# board.net
KiCad netlist of a schematic drawn in EAGLE
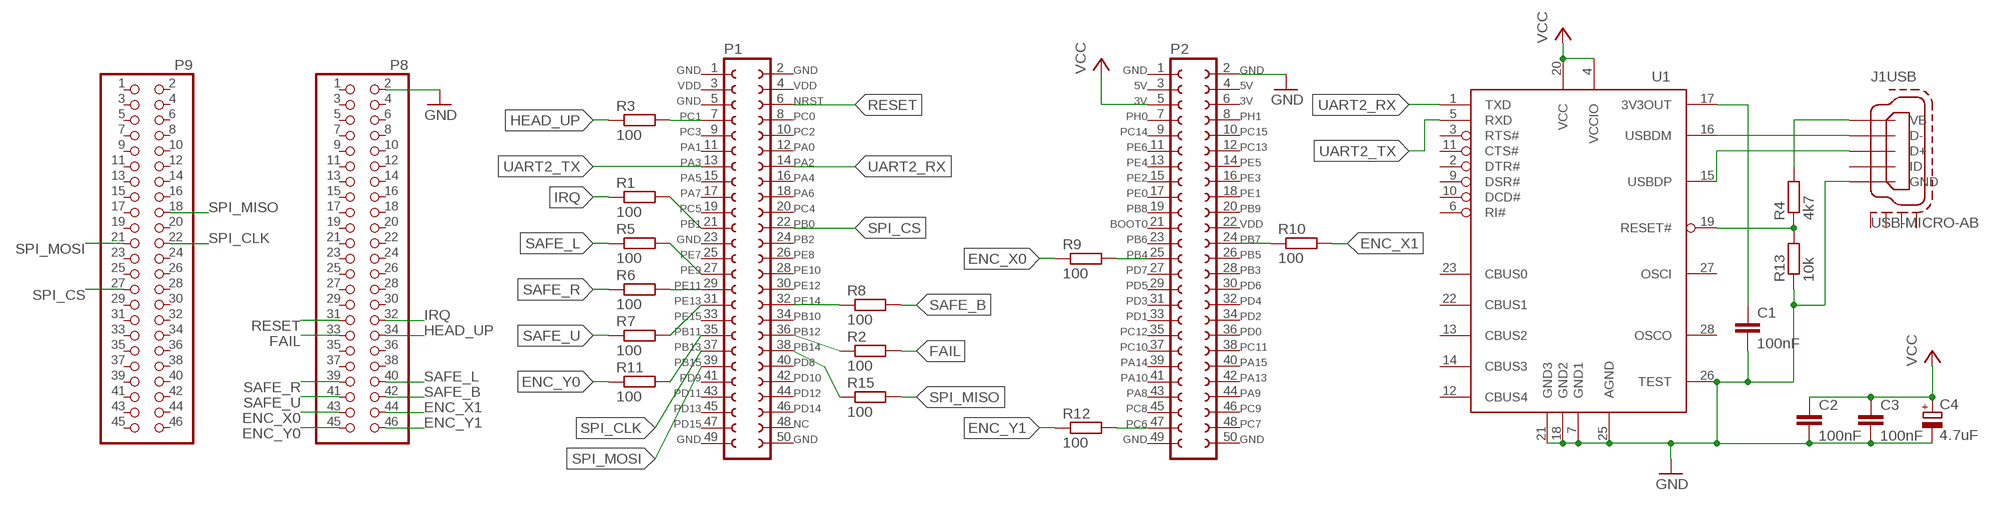
[diagram p0: schematic, sheet 1]

(export (version "E")
  (design (tool "Eeschema 10.0.6"))
  (components
    (comp (ref "C1")
      (value "100nF")
      (footprint "eagle-import:C025-024X044")
      (libsource (lib "eagle-import") (part "C-EU025-024X044"))
    )
    (comp (ref "C2")
      (value "100nF")
      (footprint "eagle-import:C025-024X044")
      (libsource (lib "eagle-import") (part "C-EU025-024X044"))
    )
    (comp (ref "C3")
      (value "100nF")
      (footprint "eagle-import:C025-024X044")
      (libsource (lib "eagle-import") (part "C-EU025-024X044"))
    )
    (comp (ref "C4")
      (value "4.7uF")
      (footprint "eagle-import:E15-5")
      (libsource (lib "eagle-import") (part "CPOL-EUE15-5AXIAL"))
    )
    (comp (ref "J1")
      (value "USB-MICRO-AB")
      (footprint "eagle-import:USB-MICRO-AB")
      (libsource (lib "eagle-import") (part "USB-MICRO-AB"))
    )
    (comp (ref "P1")
      (value "PIN-F-2X25-DISC-P1")
      (footprint "eagle-import:PIN-F-2X25")
      (libsource (lib "eagle-import") (part "PIN-F-2X25-DISC-P1"))
    )
    (comp (ref "P2")
      (value "PIN-F-2X25-DISC-P2")
      (footprint "eagle-import:PIN-F-2X25")
      (libsource (lib "eagle-import") (part "PIN-F-2X25-DISC-P2"))
    )
    (comp (ref "P8")
      (value "PIN-M-2X23")
      (footprint "eagle-import:PIN-M-2X23")
      (libsource (lib "eagle-import") (part "PIN-M-2X23"))
    )
    (comp (ref "P9")
      (value "PIN-M-2X23")
      (footprint "eagle-import:PIN-M-2X23")
      (libsource (lib "eagle-import") (part "PIN-M-2X23"))
    )
    (comp (ref "R1")
      (value "100")
      (footprint "eagle-import:0204_5")
      (libsource (lib "eagle-import") (part "R_EU"))
    )
    (comp (ref "R2")
      (value "100")
      (footprint "eagle-import:0204_5")
      (libsource (lib "eagle-import") (part "R_EU"))
    )
    (comp (ref "R3")
      (value "100")
      (footprint "eagle-import:0204_5")
      (libsource (lib "eagle-import") (part "R_EU"))
    )
    (comp (ref "R4")
      (value "4k7")
      (footprint "eagle-import:0204_5")
      (libsource (lib "eagle-import") (part "R_EU"))
    )
    (comp (ref "R5")
      (value "100")
      (footprint "eagle-import:0204_5")
      (libsource (lib "eagle-import") (part "R_EU"))
    )
    (comp (ref "R6")
      (value "100")
      (footprint "eagle-import:0204_5")
      (libsource (lib "eagle-import") (part "R_EU"))
    )
    (comp (ref "R7")
      (value "100")
      (footprint "eagle-import:0204_5")
      (libsource (lib "eagle-import") (part "R_EU"))
    )
    (comp (ref "R8")
      (value "100")
      (footprint "eagle-import:0204_5")
      (libsource (lib "eagle-import") (part "R_EU"))
    )
    (comp (ref "R9")
      (value "100")
      (footprint "eagle-import:0204_5")
      (libsource (lib "eagle-import") (part "R_EU"))
    )
    (comp (ref "R10")
      (value "100")
      (footprint "eagle-import:0204_5")
      (libsource (lib "eagle-import") (part "R_EU"))
    )
    (comp (ref "R11")
      (value "100")
      (footprint "eagle-import:0204_5")
      (libsource (lib "eagle-import") (part "R_EU"))
    )
    (comp (ref "R12")
      (value "100")
      (footprint "eagle-import:0204_5")
      (libsource (lib "eagle-import") (part "R_EU"))
    )
    (comp (ref "R13")
      (value "10k")
      (footprint "eagle-import:0204_5")
      (libsource (lib "eagle-import") (part "R_EU"))
    )
    (comp (ref "R15")
      (value "100")
      (footprint "eagle-import:0204_5")
      (libsource (lib "eagle-import") (part "R_EU"))
    )
    (comp (ref "U1")
      (value "FT232RL")
      (footprint "eagle-import:SSOP28DB")
      (libsource (lib "eagle-import") (part "FT232RL"))
    )
  )
  (nets
    (net (code "1") (name "ENC_X0") (class "Default")
      (node (ref "P8") (pin "43") (pinfunction "43_43") (pintype "passive"))
      (node (ref "R9") (pin "1") (pinfunction "1_1") (pintype "passive"))
    )
    (net (code "2") (name "ENC_X1") (class "Default")
      (node (ref "P8") (pin "44") (pinfunction "44_44") (pintype "passive"))
      (node (ref "R10") (pin "2") (pinfunction "2_2") (pintype "passive"))
    )
    (net (code "3") (name "ENC_Y0") (class "Default")
      (node (ref "P8") (pin "45") (pinfunction "45_45") (pintype "passive"))
      (node (ref "R11") (pin "1") (pinfunction "1_1") (pintype "passive"))
    )
    (net (code "4") (name "ENC_Y1") (class "Default")
      (node (ref "P8") (pin "46") (pinfunction "46_46") (pintype "passive"))
      (node (ref "R12") (pin "1") (pinfunction "1_1") (pintype "passive"))
    )
    (net (code "5") (name "FAIL") (class "Default")
      (node (ref "P8") (pin "33") (pinfunction "33_33") (pintype "passive"))
      (node (ref "R2") (pin "2") (pinfunction "2_2") (pintype "passive"))
    )
    (net (code "6") (name "GND") (class "Default")
      (node (ref "C1") (pin "2") (pinfunction "2_2") (pintype "passive"))
      (node (ref "C2") (pin "2") (pinfunction "2_2") (pintype "passive"))
      (node (ref "C3") (pin "2") (pinfunction "2_2") (pintype "passive"))
      (node (ref "C4") (pin "-") (pinfunction "-_-") (pintype "passive"))
      (node (ref "J1") (pin "P$5") (pinfunction "GND_P$5") (pintype "passive"))
      (node (ref "P2") (pin "2") (pinfunction "2_2") (pintype "passive"))
      (node (ref "P8") (pin "2") (pinfunction "2_2") (pintype "passive"))
      (node (ref "R13") (pin "1") (pinfunction "1_1") (pintype "passive"))
      (node (ref "U1") (pin "18") (pinfunction "GND2_18") (pintype "power_in"))
      (node (ref "U1") (pin "21") (pinfunction "GND3_21") (pintype "power_in"))
      (node (ref "U1") (pin "25") (pinfunction "AGND_25") (pintype "power_in"))
      (node (ref "U1") (pin "26") (pinfunction "TEST_26") (pintype "input"))
      (node (ref "U1") (pin "7") (pinfunction "GND1_7") (pintype "power_in"))
    )
    (net (code "7") (name "HEAD_UP") (class "Default")
      (node (ref "P8") (pin "34") (pinfunction "34_34") (pintype "passive"))
      (node (ref "R3") (pin "1") (pinfunction "1_1") (pintype "passive"))
    )
    (net (code "8") (name "IRQ") (class "Default")
      (node (ref "P8") (pin "32") (pinfunction "32_32") (pintype "passive"))
      (node (ref "R1") (pin "1") (pinfunction "1_1") (pintype "passive"))
    )
    (net (code "9") (name "Net-(J1B-D+)") (class "Default")
      (node (ref "J1") (pin "P$3") (pinfunction "D+_P$3") (pintype "passive"))
      (node (ref "U1") (pin "15") (pinfunction "USBDP_15") (pintype "bidirectional"))
    )
    (net (code "10") (name "Net-(J1B-D-)") (class "Default")
      (node (ref "J1") (pin "P$2") (pinfunction "D-_P$2") (pintype "passive"))
      (node (ref "U1") (pin "16") (pinfunction "USBDM_16") (pintype "bidirectional"))
    )
    (net (code "11") (name "Net-(J1B-VB)") (class "Default")
      (node (ref "J1") (pin "P$1") (pinfunction "VB_P$1") (pintype "passive"))
      (node (ref "R4") (pin "2") (pinfunction "2_2") (pintype "passive"))
    )
    (net (code "12") (name "Net-(P1-Pad7)") (class "Default")
      (node (ref "P1") (pin "7") (pinfunction "7_7") (pintype "passive"))
      (node (ref "R3") (pin "2") (pinfunction "2_2") (pintype "passive"))
    )
    (net (code "13") (name "Net-(P1-Pad21)") (class "Default")
      (node (ref "P1") (pin "21") (pinfunction "21_21") (pintype "passive"))
      (node (ref "R1") (pin "2") (pinfunction "2_2") (pintype "passive"))
    )
    (net (code "14") (name "Net-(P1-Pad27)") (class "Default")
      (node (ref "P1") (pin "27") (pinfunction "27_27") (pintype "passive"))
      (node (ref "R5") (pin "2") (pinfunction "2_2") (pintype "passive"))
    )
    (net (code "15") (name "Net-(P1-Pad29)") (class "Default")
      (node (ref "P1") (pin "29") (pinfunction "29_29") (pintype "passive"))
      (node (ref "R6") (pin "2") (pinfunction "2_2") (pintype "passive"))
    )
    (net (code "16") (name "Net-(P1-Pad31)") (class "Default")
      (node (ref "P1") (pin "31") (pinfunction "31_31") (pintype "passive"))
      (node (ref "R7") (pin "2") (pinfunction "2_2") (pintype "passive"))
    )
    (net (code "17") (name "Net-(P1-Pad32)") (class "Default")
      (node (ref "P1") (pin "32") (pinfunction "32_32") (pintype "passive"))
      (node (ref "R8") (pin "1") (pinfunction "1_1") (pintype "passive"))
    )
    (net (code "18") (name "Net-(P1-Pad35)") (class "Default")
      (node (ref "P1") (pin "35") (pinfunction "35_35") (pintype "passive"))
      (node (ref "R11") (pin "2") (pinfunction "2_2") (pintype "passive"))
    )
    (net (code "19") (name "Net-(P1-Pad36)") (class "Default")
      (node (ref "P1") (pin "36") (pinfunction "36_36") (pintype "passive"))
      (node (ref "R2") (pin "1") (pinfunction "1_1") (pintype "passive"))
    )
    (net (code "20") (name "Net-(P1-Pad38)") (class "Default")
      (node (ref "P1") (pin "38") (pinfunction "38_38") (pintype "passive"))
      (node (ref "R15") (pin "1") (pinfunction "1_1") (pintype "passive"))
    )
    (net (code "21") (name "Net-(P2-Pad24)") (class "Default")
      (node (ref "P2") (pin "24") (pinfunction "24_24") (pintype "passive"))
      (node (ref "R10") (pin "1") (pinfunction "1_1") (pintype "passive"))
    )
    (net (code "22") (name "Net-(P2-Pad25)") (class "Default")
      (node (ref "P2") (pin "25") (pinfunction "25_25") (pintype "passive"))
      (node (ref "R9") (pin "2") (pinfunction "2_2") (pintype "passive"))
    )
    (net (code "23") (name "Net-(P2-Pad47)") (class "Default")
      (node (ref "P2") (pin "47") (pinfunction "47_47") (pintype "passive"))
      (node (ref "R12") (pin "2") (pinfunction "2_2") (pintype "passive"))
    )
    (net (code "24") (name "Net-(U1-3V3OUT)") (class "Default")
      (node (ref "C1") (pin "1") (pinfunction "1_1") (pintype "passive"))
      (node (ref "U1") (pin "17") (pinfunction "3V3OUT_17") (pintype "output"))
    )
    (net (code "25") (name "Net-(U1-RESET#)") (class "Default")
      (node (ref "R13") (pin "2") (pinfunction "2_2") (pintype "passive"))
      (node (ref "R4") (pin "1") (pinfunction "1_1") (pintype "passive"))
      (node (ref "U1") (pin "19") (pinfunction "RESET#_19") (pintype "input"))
    )
    (net (code "26") (name "RESET") (class "Default")
      (node (ref "P1") (pin "6") (pinfunction "6_6") (pintype "passive"))
      (node (ref "P8") (pin "31") (pinfunction "31_31") (pintype "passive"))
    )
    (net (code "27") (name "SAFE_B") (class "Default")
      (node (ref "P8") (pin "42") (pinfunction "42_42") (pintype "passive"))
      (node (ref "R8") (pin "2") (pinfunction "2_2") (pintype "passive"))
    )
    (net (code "28") (name "SAFE_L") (class "Default")
      (node (ref "P8") (pin "40") (pinfunction "40_40") (pintype "passive"))
      (node (ref "R5") (pin "1") (pinfunction "1_1") (pintype "passive"))
    )
    (net (code "29") (name "SAFE_R") (class "Default")
      (node (ref "P8") (pin "39") (pinfunction "39_39") (pintype "passive"))
      (node (ref "R6") (pin "1") (pinfunction "1_1") (pintype "passive"))
    )
    (net (code "30") (name "SAFE_U") (class "Default")
      (node (ref "P8") (pin "41") (pinfunction "41_41") (pintype "passive"))
      (node (ref "R7") (pin "1") (pinfunction "1_1") (pintype "passive"))
    )
    (net (code "31") (name "SPI_CLK") (class "Default")
      (node (ref "P1") (pin "37") (pinfunction "37_37") (pintype "passive"))
      (node (ref "P9") (pin "22") (pinfunction "22_22") (pintype "passive"))
    )
    (net (code "32") (name "SPI_CS") (class "Default")
      (node (ref "P1") (pin "22") (pinfunction "22_22") (pintype "passive"))
      (node (ref "P9") (pin "27") (pinfunction "27_27") (pintype "passive"))
    )
    (net (code "33") (name "SPI_MISO") (class "Default")
      (node (ref "P9") (pin "18") (pinfunction "18_18") (pintype "passive"))
      (node (ref "R15") (pin "2") (pinfunction "2_2") (pintype "passive"))
    )
    (net (code "34") (name "SPI_MOSI") (class "Default")
      (node (ref "P1") (pin "39") (pinfunction "39_39") (pintype "passive"))
      (node (ref "P9") (pin "21") (pinfunction "21_21") (pintype "passive"))
    )
    (net (code "35") (name "UART2_RX") (class "Default")
      (node (ref "P1") (pin "14") (pinfunction "14_14") (pintype "passive"))
      (node (ref "U1") (pin "1") (pinfunction "TXD_1") (pintype "output"))
    )
    (net (code "36") (name "UART2_TX") (class "Default")
      (node (ref "P1") (pin "13") (pinfunction "13_13") (pintype "passive"))
      (node (ref "U1") (pin "5") (pinfunction "RXD_5") (pintype "input"))
    )
    (net (code "37") (name "VCC") (class "Default")
      (node (ref "C2") (pin "1") (pinfunction "1_1") (pintype "passive"))
      (node (ref "C3") (pin "1") (pinfunction "1_1") (pintype "passive"))
      (node (ref "C4") (pin "+") (pinfunction "+_+") (pintype "passive"))
      (node (ref "P2") (pin "5") (pinfunction "5_5") (pintype "passive"))
      (node (ref "U1") (pin "20") (pinfunction "VCC_20") (pintype "power_in"))
      (node (ref "U1") (pin "4") (pinfunction "VCCIO_4") (pintype "power_in"))
    )
    (net (code "38") (name "unconnected-(J1A-S1-PadSHIELD1)") (class "Default")
      (node (ref "J1") (pin "SHIELD1") (pinfunction "S1_SHIELD1") (pintype "passive"))
    )
    (net (code "39") (name "unconnected-(J1A-S2-PadSHIELD2)") (class "Default")
      (node (ref "J1") (pin "SHIELD2") (pinfunction "S2_SHIELD2") (pintype "passive"))
    )
    (net (code "40") (name "unconnected-(J1A-S3-PadSHIELD3)") (class "Default")
      (node (ref "J1") (pin "SHIELD3") (pinfunction "S3_SHIELD3") (pintype "passive"))
    )
    (net (code "41") (name "unconnected-(J1A-S4-PadSHIELD4)") (class "Default")
      (node (ref "J1") (pin "SHIELD4") (pinfunction "S4_SHIELD4") (pintype "passive"))
    )
    (net (code "42") (name "unconnected-(J1B-ID-PadP$4)") (class "Default")
      (node (ref "J1") (pin "P$4") (pinfunction "ID_P$4") (pintype "passive"))
    )
    (net (code "43") (name "unconnected-(P1-Pad1)") (class "Default")
      (node (ref "P1") (pin "1") (pinfunction "1_1") (pintype "passive"))
    )
    (net (code "44") (name "unconnected-(P1-Pad2)") (class "Default")
      (node (ref "P1") (pin "2") (pinfunction "2_2") (pintype "passive"))
    )
    (net (code "45") (name "unconnected-(P1-Pad3)") (class "Default")
      (node (ref "P1") (pin "3") (pinfunction "3_3") (pintype "passive"))
    )
    (net (code "46") (name "unconnected-(P1-Pad4)") (class "Default")
      (node (ref "P1") (pin "4") (pinfunction "4_4") (pintype "passive"))
    )
    (net (code "47") (name "unconnected-(P1-Pad5)") (class "Default")
      (node (ref "P1") (pin "5") (pinfunction "5_5") (pintype "passive"))
    )
    (net (code "48") (name "unconnected-(P1-Pad8)") (class "Default")
      (node (ref "P1") (pin "8") (pinfunction "8_8") (pintype "passive"))
    )
    (net (code "49") (name "unconnected-(P1-Pad9)") (class "Default")
      (node (ref "P1") (pin "9") (pinfunction "9_9") (pintype "passive"))
    )
    (net (code "50") (name "unconnected-(P1-Pad10)") (class "Default")
      (node (ref "P1") (pin "10") (pinfunction "10_10") (pintype "passive"))
    )
    (net (code "51") (name "unconnected-(P1-Pad11)") (class "Default")
      (node (ref "P1") (pin "11") (pinfunction "11_11") (pintype "passive"))
    )
    (net (code "52") (name "unconnected-(P1-Pad12)") (class "Default")
      (node (ref "P1") (pin "12") (pinfunction "12_12") (pintype "passive"))
    )
    (net (code "53") (name "unconnected-(P1-Pad15)") (class "Default")
      (node (ref "P1") (pin "15") (pinfunction "15_15") (pintype "passive"))
    )
    (net (code "54") (name "unconnected-(P1-Pad16)") (class "Default")
      (node (ref "P1") (pin "16") (pinfunction "16_16") (pintype "passive"))
    )
    (net (code "55") (name "unconnected-(P1-Pad17)") (class "Default")
      (node (ref "P1") (pin "17") (pinfunction "17_17") (pintype "passive"))
    )
    (net (code "56") (name "unconnected-(P1-Pad18)") (class "Default")
      (node (ref "P1") (pin "18") (pinfunction "18_18") (pintype "passive"))
    )
    (net (code "57") (name "unconnected-(P1-Pad19)") (class "Default")
      (node (ref "P1") (pin "19") (pinfunction "19_19") (pintype "passive"))
    )
    (net (code "58") (name "unconnected-(P1-Pad20)") (class "Default")
      (node (ref "P1") (pin "20") (pinfunction "20_20") (pintype "passive"))
    )
    (net (code "59") (name "unconnected-(P1-Pad23)") (class "Default")
      (node (ref "P1") (pin "23") (pinfunction "23_23") (pintype "passive"))
    )
    (net (code "60") (name "unconnected-(P1-Pad24)") (class "Default")
      (node (ref "P1") (pin "24") (pinfunction "24_24") (pintype "passive"))
    )
    (net (code "61") (name "unconnected-(P1-Pad25)") (class "Default")
      (node (ref "P1") (pin "25") (pinfunction "25_25") (pintype "passive"))
    )
    (net (code "62") (name "unconnected-(P1-Pad26)") (class "Default")
      (node (ref "P1") (pin "26") (pinfunction "26_26") (pintype "passive"))
    )
    (net (code "63") (name "unconnected-(P1-Pad28)") (class "Default")
      (node (ref "P1") (pin "28") (pinfunction "28_28") (pintype "passive"))
    )
    (net (code "64") (name "unconnected-(P1-Pad30)") (class "Default")
      (node (ref "P1") (pin "30") (pinfunction "30_30") (pintype "passive"))
    )
    (net (code "65") (name "unconnected-(P1-Pad33)") (class "Default")
      (node (ref "P1") (pin "33") (pinfunction "33_33") (pintype "passive"))
    )
    (net (code "66") (name "unconnected-(P1-Pad34)") (class "Default")
      (node (ref "P1") (pin "34") (pinfunction "34_34") (pintype "passive"))
    )
    (net (code "67") (name "unconnected-(P1-Pad40)") (class "Default")
      (node (ref "P1") (pin "40") (pinfunction "40_40") (pintype "passive"))
    )
    (net (code "68") (name "unconnected-(P1-Pad41)") (class "Default")
      (node (ref "P1") (pin "41") (pinfunction "41_41") (pintype "passive"))
    )
    (net (code "69") (name "unconnected-(P1-Pad42)") (class "Default")
      (node (ref "P1") (pin "42") (pinfunction "42_42") (pintype "passive"))
    )
    (net (code "70") (name "unconnected-(P1-Pad43)") (class "Default")
      (node (ref "P1") (pin "43") (pinfunction "43_43") (pintype "passive"))
    )
    (net (code "71") (name "unconnected-(P1-Pad44)") (class "Default")
      (node (ref "P1") (pin "44") (pinfunction "44_44") (pintype "passive"))
    )
    (net (code "72") (name "unconnected-(P1-Pad45)") (class "Default")
      (node (ref "P1") (pin "45") (pinfunction "45_45") (pintype "passive"))
    )
    (net (code "73") (name "unconnected-(P1-Pad46)") (class "Default")
      (node (ref "P1") (pin "46") (pinfunction "46_46") (pintype "passive"))
    )
    (net (code "74") (name "unconnected-(P1-Pad47)") (class "Default")
      (node (ref "P1") (pin "47") (pinfunction "47_47") (pintype "passive"))
    )
    (net (code "75") (name "unconnected-(P1-Pad48)") (class "Default")
      (node (ref "P1") (pin "48") (pinfunction "48_48") (pintype "passive"))
    )
    (net (code "76") (name "unconnected-(P1-Pad49)") (class "Default")
      (node (ref "P1") (pin "49") (pinfunction "49_49") (pintype "passive"))
    )
    (net (code "77") (name "unconnected-(P1-Pad50)") (class "Default")
      (node (ref "P1") (pin "50") (pinfunction "50_50") (pintype "passive"))
    )
    (net (code "78") (name "unconnected-(P2-Pad1)") (class "Default")
      (node (ref "P2") (pin "1") (pinfunction "1_1") (pintype "passive"))
    )
    (net (code "79") (name "unconnected-(P2-Pad3)") (class "Default")
      (node (ref "P2") (pin "3") (pinfunction "3_3") (pintype "passive"))
    )
    (net (code "80") (name "unconnected-(P2-Pad4)") (class "Default")
      (node (ref "P2") (pin "4") (pinfunction "4_4") (pintype "passive"))
    )
    (net (code "81") (name "unconnected-(P2-Pad6)") (class "Default")
      (node (ref "P2") (pin "6") (pinfunction "6_6") (pintype "passive"))
    )
    (net (code "82") (name "unconnected-(P2-Pad7)") (class "Default")
      (node (ref "P2") (pin "7") (pinfunction "7_7") (pintype "passive"))
    )
    (net (code "83") (name "unconnected-(P2-Pad8)") (class "Default")
      (node (ref "P2") (pin "8") (pinfunction "8_8") (pintype "passive"))
    )
    (net (code "84") (name "unconnected-(P2-Pad9)") (class "Default")
      (node (ref "P2") (pin "9") (pinfunction "9_9") (pintype "passive"))
    )
    (net (code "85") (name "unconnected-(P2-Pad10)") (class "Default")
      (node (ref "P2") (pin "10") (pinfunction "10_10") (pintype "passive"))
    )
    (net (code "86") (name "unconnected-(P2-Pad11)") (class "Default")
      (node (ref "P2") (pin "11") (pinfunction "11_11") (pintype "passive"))
    )
    (net (code "87") (name "unconnected-(P2-Pad12)") (class "Default")
      (node (ref "P2") (pin "12") (pinfunction "12_12") (pintype "passive"))
    )
    (net (code "88") (name "unconnected-(P2-Pad13)") (class "Default")
      (node (ref "P2") (pin "13") (pinfunction "13_13") (pintype "passive"))
    )
    (net (code "89") (name "unconnected-(P2-Pad14)") (class "Default")
      (node (ref "P2") (pin "14") (pinfunction "14_14") (pintype "passive"))
    )
    (net (code "90") (name "unconnected-(P2-Pad15)") (class "Default")
      (node (ref "P2") (pin "15") (pinfunction "15_15") (pintype "passive"))
    )
    (net (code "91") (name "unconnected-(P2-Pad16)") (class "Default")
      (node (ref "P2") (pin "16") (pinfunction "16_16") (pintype "passive"))
    )
    (net (code "92") (name "unconnected-(P2-Pad17)") (class "Default")
      (node (ref "P2") (pin "17") (pinfunction "17_17") (pintype "passive"))
    )
    (net (code "93") (name "unconnected-(P2-Pad18)") (class "Default")
      (node (ref "P2") (pin "18") (pinfunction "18_18") (pintype "passive"))
    )
    (net (code "94") (name "unconnected-(P2-Pad19)") (class "Default")
      (node (ref "P2") (pin "19") (pinfunction "19_19") (pintype "passive"))
    )
    (net (code "95") (name "unconnected-(P2-Pad20)") (class "Default")
      (node (ref "P2") (pin "20") (pinfunction "20_20") (pintype "passive"))
    )
    (net (code "96") (name "unconnected-(P2-Pad21)") (class "Default")
      (node (ref "P2") (pin "21") (pinfunction "21_21") (pintype "passive"))
    )
    (net (code "97") (name "unconnected-(P2-Pad22)") (class "Default")
      (node (ref "P2") (pin "22") (pinfunction "22_22") (pintype "passive"))
    )
    (net (code "98") (name "unconnected-(P2-Pad23)") (class "Default")
      (node (ref "P2") (pin "23") (pinfunction "23_23") (pintype "passive"))
    )
    (net (code "99") (name "unconnected-(P2-Pad26)") (class "Default")
      (node (ref "P2") (pin "26") (pinfunction "26_26") (pintype "passive"))
    )
    (net (code "100") (name "unconnected-(P2-Pad27)") (class "Default")
      (node (ref "P2") (pin "27") (pinfunction "27_27") (pintype "passive"))
    )
    (net (code "101") (name "unconnected-(P2-Pad28)") (class "Default")
      (node (ref "P2") (pin "28") (pinfunction "28_28") (pintype "passive"))
    )
    (net (code "102") (name "unconnected-(P2-Pad29)") (class "Default")
      (node (ref "P2") (pin "29") (pinfunction "29_29") (pintype "passive"))
    )
    (net (code "103") (name "unconnected-(P2-Pad30)") (class "Default")
      (node (ref "P2") (pin "30") (pinfunction "30_30") (pintype "passive"))
    )
    (net (code "104") (name "unconnected-(P2-Pad31)") (class "Default")
      (node (ref "P2") (pin "31") (pinfunction "31_31") (pintype "passive"))
    )
    (net (code "105") (name "unconnected-(P2-Pad32)") (class "Default")
      (node (ref "P2") (pin "32") (pinfunction "32_32") (pintype "passive"))
    )
    (net (code "106") (name "unconnected-(P2-Pad33)") (class "Default")
      (node (ref "P2") (pin "33") (pinfunction "33_33") (pintype "passive"))
    )
    (net (code "107") (name "unconnected-(P2-Pad34)") (class "Default")
      (node (ref "P2") (pin "34") (pinfunction "34_34") (pintype "passive"))
    )
    (net (code "108") (name "unconnected-(P2-Pad35)") (class "Default")
      (node (ref "P2") (pin "35") (pinfunction "35_35") (pintype "passive"))
    )
    (net (code "109") (name "unconnected-(P2-Pad36)") (class "Default")
      (node (ref "P2") (pin "36") (pinfunction "36_36") (pintype "passive"))
    )
    (net (code "110") (name "unconnected-(P2-Pad37)") (class "Default")
      (node (ref "P2") (pin "37") (pinfunction "37_37") (pintype "passive"))
    )
    (net (code "111") (name "unconnected-(P2-Pad38)") (class "Default")
      (node (ref "P2") (pin "38") (pinfunction "38_38") (pintype "passive"))
    )
    (net (code "112") (name "unconnected-(P2-Pad39)") (class "Default")
      (node (ref "P2") (pin "39") (pinfunction "39_39") (pintype "passive"))
    )
    (net (code "113") (name "unconnected-(P2-Pad40)") (class "Default")
      (node (ref "P2") (pin "40") (pinfunction "40_40") (pintype "passive"))
    )
    (net (code "114") (name "unconnected-(P2-Pad41)") (class "Default")
      (node (ref "P2") (pin "41") (pinfunction "41_41") (pintype "passive"))
    )
    (net (code "115") (name "unconnected-(P2-Pad42)") (class "Default")
      (node (ref "P2") (pin "42") (pinfunction "42_42") (pintype "passive"))
    )
    (net (code "116") (name "unconnected-(P2-Pad43)") (class "Default")
      (node (ref "P2") (pin "43") (pinfunction "43_43") (pintype "passive"))
    )
    (net (code "117") (name "unconnected-(P2-Pad44)") (class "Default")
      (node (ref "P2") (pin "44") (pinfunction "44_44") (pintype "passive"))
    )
    (net (code "118") (name "unconnected-(P2-Pad45)") (class "Default")
      (node (ref "P2") (pin "45") (pinfunction "45_45") (pintype "passive"))
    )
    (net (code "119") (name "unconnected-(P2-Pad46)") (class "Default")
      (node (ref "P2") (pin "46") (pinfunction "46_46") (pintype "passive"))
    )
    (net (code "120") (name "unconnected-(P2-Pad48)") (class "Default")
      (node (ref "P2") (pin "48") (pinfunction "48_48") (pintype "passive"))
    )
    (net (code "121") (name "unconnected-(P2-Pad49)") (class "Default")
      (node (ref "P2") (pin "49") (pinfunction "49_49") (pintype "passive"))
    )
    (net (code "122") (name "unconnected-(P2-Pad50)") (class "Default")
      (node (ref "P2") (pin "50") (pinfunction "50_50") (pintype "passive"))
    )
    (net (code "123") (name "unconnected-(P8-Pad1)") (class "Default")
      (node (ref "P8") (pin "1") (pinfunction "1_1") (pintype "passive"))
    )
    (net (code "124") (name "unconnected-(P8-Pad3)") (class "Default")
      (node (ref "P8") (pin "3") (pinfunction "3_3") (pintype "passive"))
    )
    (net (code "125") (name "unconnected-(P8-Pad4)") (class "Default")
      (node (ref "P8") (pin "4") (pinfunction "4_4") (pintype "passive"))
    )
    (net (code "126") (name "unconnected-(P8-Pad5)") (class "Default")
      (node (ref "P8") (pin "5") (pinfunction "5_5") (pintype "passive"))
    )
    (net (code "127") (name "unconnected-(P8-Pad6)") (class "Default")
      (node (ref "P8") (pin "6") (pinfunction "6_6") (pintype "passive"))
    )
    (net (code "128") (name "unconnected-(P8-Pad7)") (class "Default")
      (node (ref "P8") (pin "7") (pinfunction "7_7") (pintype "passive"))
    )
    (net (code "129") (name "unconnected-(P8-Pad8)") (class "Default")
      (node (ref "P8") (pin "8") (pinfunction "8_8") (pintype "passive"))
    )
    (net (code "130") (name "unconnected-(P8-Pad9)") (class "Default")
      (node (ref "P8") (pin "9") (pinfunction "9_9") (pintype "passive"))
    )
    (net (code "131") (name "unconnected-(P8-Pad10)") (class "Default")
      (node (ref "P8") (pin "10") (pinfunction "10_10") (pintype "passive"))
    )
    (net (code "132") (name "unconnected-(P8-Pad11)") (class "Default")
      (node (ref "P8") (pin "11") (pinfunction "11_11") (pintype "passive"))
    )
    (net (code "133") (name "unconnected-(P8-Pad12)") (class "Default")
      (node (ref "P8") (pin "12") (pinfunction "12_12") (pintype "passive"))
    )
    (net (code "134") (name "unconnected-(P8-Pad13)") (class "Default")
      (node (ref "P8") (pin "13") (pinfunction "13_13") (pintype "passive"))
    )
    (net (code "135") (name "unconnected-(P8-Pad14)") (class "Default")
      (node (ref "P8") (pin "14") (pinfunction "14_14") (pintype "passive"))
    )
    (net (code "136") (name "unconnected-(P8-Pad15)") (class "Default")
      (node (ref "P8") (pin "15") (pinfunction "15_15") (pintype "passive"))
    )
    (net (code "137") (name "unconnected-(P8-Pad16)") (class "Default")
      (node (ref "P8") (pin "16") (pinfunction "16_16") (pintype "passive"))
    )
    (net (code "138") (name "unconnected-(P8-Pad17)") (class "Default")
      (node (ref "P8") (pin "17") (pinfunction "17_17") (pintype "passive"))
    )
    (net (code "139") (name "unconnected-(P8-Pad18)") (class "Default")
      (node (ref "P8") (pin "18") (pinfunction "18_18") (pintype "passive"))
    )
    (net (code "140") (name "unconnected-(P8-Pad19)") (class "Default")
      (node (ref "P8") (pin "19") (pinfunction "19_19") (pintype "passive"))
    )
    (net (code "141") (name "unconnected-(P8-Pad20)") (class "Default")
      (node (ref "P8") (pin "20") (pinfunction "20_20") (pintype "passive"))
    )
    (net (code "142") (name "unconnected-(P8-Pad21)") (class "Default")
      (node (ref "P8") (pin "21") (pinfunction "21_21") (pintype "passive"))
    )
    (net (code "143") (name "unconnected-(P8-Pad22)") (class "Default")
      (node (ref "P8") (pin "22") (pinfunction "22_22") (pintype "passive"))
    )
    (net (code "144") (name "unconnected-(P8-Pad23)") (class "Default")
      (node (ref "P8") (pin "23") (pinfunction "23_23") (pintype "passive"))
    )
    (net (code "145") (name "unconnected-(P8-Pad24)") (class "Default")
      (node (ref "P8") (pin "24") (pinfunction "24_24") (pintype "passive"))
    )
    (net (code "146") (name "unconnected-(P8-Pad25)") (class "Default")
      (node (ref "P8") (pin "25") (pinfunction "25_25") (pintype "passive"))
    )
    (net (code "147") (name "unconnected-(P8-Pad26)") (class "Default")
      (node (ref "P8") (pin "26") (pinfunction "26_26") (pintype "passive"))
    )
    (net (code "148") (name "unconnected-(P8-Pad27)") (class "Default")
      (node (ref "P8") (pin "27") (pinfunction "27_27") (pintype "passive"))
    )
    (net (code "149") (name "unconnected-(P8-Pad28)") (class "Default")
      (node (ref "P8") (pin "28") (pinfunction "28_28") (pintype "passive"))
    )
    (net (code "150") (name "unconnected-(P8-Pad29)") (class "Default")
      (node (ref "P8") (pin "29") (pinfunction "29_29") (pintype "passive"))
    )
    (net (code "151") (name "unconnected-(P8-Pad30)") (class "Default")
      (node (ref "P8") (pin "30") (pinfunction "30_30") (pintype "passive"))
    )
    (net (code "152") (name "unconnected-(P8-Pad35)") (class "Default")
      (node (ref "P8") (pin "35") (pinfunction "35_35") (pintype "passive"))
    )
    (net (code "153") (name "unconnected-(P8-Pad36)") (class "Default")
      (node (ref "P8") (pin "36") (pinfunction "36_36") (pintype "passive"))
    )
    (net (code "154") (name "unconnected-(P8-Pad37)") (class "Default")
      (node (ref "P8") (pin "37") (pinfunction "37_37") (pintype "passive"))
    )
    (net (code "155") (name "unconnected-(P8-Pad38)") (class "Default")
      (node (ref "P8") (pin "38") (pinfunction "38_38") (pintype "passive"))
    )
    (net (code "156") (name "unconnected-(P9-Pad1)") (class "Default")
      (node (ref "P9") (pin "1") (pinfunction "1_1") (pintype "passive"))
    )
    (net (code "157") (name "unconnected-(P9-Pad2)") (class "Default")
      (node (ref "P9") (pin "2") (pinfunction "2_2") (pintype "passive"))
    )
    (net (code "158") (name "unconnected-(P9-Pad3)") (class "Default")
      (node (ref "P9") (pin "3") (pinfunction "3_3") (pintype "passive"))
    )
    (net (code "159") (name "unconnected-(P9-Pad4)") (class "Default")
      (node (ref "P9") (pin "4") (pinfunction "4_4") (pintype "passive"))
    )
    (net (code "160") (name "unconnected-(P9-Pad5)") (class "Default")
      (node (ref "P9") (pin "5") (pinfunction "5_5") (pintype "passive"))
    )
    (net (code "161") (name "unconnected-(P9-Pad6)") (class "Default")
      (node (ref "P9") (pin "6") (pinfunction "6_6") (pintype "passive"))
    )
    (net (code "162") (name "unconnected-(P9-Pad7)") (class "Default")
      (node (ref "P9") (pin "7") (pinfunction "7_7") (pintype "passive"))
    )
    (net (code "163") (name "unconnected-(P9-Pad8)") (class "Default")
      (node (ref "P9") (pin "8") (pinfunction "8_8") (pintype "passive"))
    )
    (net (code "164") (name "unconnected-(P9-Pad9)") (class "Default")
      (node (ref "P9") (pin "9") (pinfunction "9_9") (pintype "passive"))
    )
    (net (code "165") (name "unconnected-(P9-Pad10)") (class "Default")
      (node (ref "P9") (pin "10") (pinfunction "10_10") (pintype "passive"))
    )
    (net (code "166") (name "unconnected-(P9-Pad11)") (class "Default")
      (node (ref "P9") (pin "11") (pinfunction "11_11") (pintype "passive"))
    )
    (net (code "167") (name "unconnected-(P9-Pad12)") (class "Default")
      (node (ref "P9") (pin "12") (pinfunction "12_12") (pintype "passive"))
    )
    (net (code "168") (name "unconnected-(P9-Pad13)") (class "Default")
      (node (ref "P9") (pin "13") (pinfunction "13_13") (pintype "passive"))
    )
    (net (code "169") (name "unconnected-(P9-Pad14)") (class "Default")
      (node (ref "P9") (pin "14") (pinfunction "14_14") (pintype "passive"))
    )
    (net (code "170") (name "unconnected-(P9-Pad15)") (class "Default")
      (node (ref "P9") (pin "15") (pinfunction "15_15") (pintype "passive"))
    )
    (net (code "171") (name "unconnected-(P9-Pad16)") (class "Default")
      (node (ref "P9") (pin "16") (pinfunction "16_16") (pintype "passive"))
    )
    (net (code "172") (name "unconnected-(P9-Pad17)") (class "Default")
      (node (ref "P9") (pin "17") (pinfunction "17_17") (pintype "passive"))
    )
    (net (code "173") (name "unconnected-(P9-Pad19)") (class "Default")
      (node (ref "P9") (pin "19") (pinfunction "19_19") (pintype "passive"))
    )
    (net (code "174") (name "unconnected-(P9-Pad20)") (class "Default")
      (node (ref "P9") (pin "20") (pinfunction "20_20") (pintype "passive"))
    )
    (net (code "175") (name "unconnected-(P9-Pad23)") (class "Default")
      (node (ref "P9") (pin "23") (pinfunction "23_23") (pintype "passive"))
    )
    (net (code "176") (name "unconnected-(P9-Pad24)") (class "Default")
      (node (ref "P9") (pin "24") (pinfunction "24_24") (pintype "passive"))
    )
    (net (code "177") (name "unconnected-(P9-Pad25)") (class "Default")
      (node (ref "P9") (pin "25") (pinfunction "25_25") (pintype "passive"))
    )
    (net (code "178") (name "unconnected-(P9-Pad26)") (class "Default")
      (node (ref "P9") (pin "26") (pinfunction "26_26") (pintype "passive"))
    )
    (net (code "179") (name "unconnected-(P9-Pad28)") (class "Default")
      (node (ref "P9") (pin "28") (pinfunction "28_28") (pintype "passive"))
    )
    (net (code "180") (name "unconnected-(P9-Pad29)") (class "Default")
      (node (ref "P9") (pin "29") (pinfunction "29_29") (pintype "passive"))
    )
    (net (code "181") (name "unconnected-(P9-Pad30)") (class "Default")
      (node (ref "P9") (pin "30") (pinfunction "30_30") (pintype "passive"))
    )
    (net (code "182") (name "unconnected-(P9-Pad31)") (class "Default")
      (node (ref "P9") (pin "31") (pinfunction "31_31") (pintype "passive"))
    )
    (net (code "183") (name "unconnected-(P9-Pad32)") (class "Default")
      (node (ref "P9") (pin "32") (pinfunction "32_32") (pintype "passive"))
    )
    (net (code "184") (name "unconnected-(P9-Pad33)") (class "Default")
      (node (ref "P9") (pin "33") (pinfunction "33_33") (pintype "passive"))
    )
    (net (code "185") (name "unconnected-(P9-Pad34)") (class "Default")
      (node (ref "P9") (pin "34") (pinfunction "34_34") (pintype "passive"))
    )
    (net (code "186") (name "unconnected-(P9-Pad35)") (class "Default")
      (node (ref "P9") (pin "35") (pinfunction "35_35") (pintype "passive"))
    )
    (net (code "187") (name "unconnected-(P9-Pad36)") (class "Default")
      (node (ref "P9") (pin "36") (pinfunction "36_36") (pintype "passive"))
    )
    (net (code "188") (name "unconnected-(P9-Pad37)") (class "Default")
      (node (ref "P9") (pin "37") (pinfunction "37_37") (pintype "passive"))
    )
    (net (code "189") (name "unconnected-(P9-Pad38)") (class "Default")
      (node (ref "P9") (pin "38") (pinfunction "38_38") (pintype "passive"))
    )
    (net (code "190") (name "unconnected-(P9-Pad39)") (class "Default")
      (node (ref "P9") (pin "39") (pinfunction "39_39") (pintype "passive"))
    )
    (net (code "191") (name "unconnected-(P9-Pad40)") (class "Default")
      (node (ref "P9") (pin "40") (pinfunction "40_40") (pintype "passive"))
    )
    (net (code "192") (name "unconnected-(P9-Pad41)") (class "Default")
      (node (ref "P9") (pin "41") (pinfunction "41_41") (pintype "passive"))
    )
    (net (code "193") (name "unconnected-(P9-Pad42)") (class "Default")
      (node (ref "P9") (pin "42") (pinfunction "42_42") (pintype "passive"))
    )
    (net (code "194") (name "unconnected-(P9-Pad43)") (class "Default")
      (node (ref "P9") (pin "43") (pinfunction "43_43") (pintype "passive"))
    )
    (net (code "195") (name "unconnected-(P9-Pad44)") (class "Default")
      (node (ref "P9") (pin "44") (pinfunction "44_44") (pintype "passive"))
    )
    (net (code "196") (name "unconnected-(P9-Pad45)") (class "Default")
      (node (ref "P9") (pin "45") (pinfunction "45_45") (pintype "passive"))
    )
    (net (code "197") (name "unconnected-(P9-Pad46)") (class "Default")
      (node (ref "P9") (pin "46") (pinfunction "46_46") (pintype "passive"))
    )
    (net (code "198") (name "unconnected-(U1-CBUS0-Pad23)") (class "Default")
      (node (ref "U1") (pin "23") (pinfunction "CBUS0_23") (pintype "bidirectional"))
    )
    (net (code "199") (name "unconnected-(U1-CBUS1-Pad22)") (class "Default")
      (node (ref "U1") (pin "22") (pinfunction "CBUS1_22") (pintype "bidirectional"))
    )
    (net (code "200") (name "unconnected-(U1-CBUS2-Pad13)") (class "Default")
      (node (ref "U1") (pin "13") (pinfunction "CBUS2_13") (pintype "bidirectional"))
    )
    (net (code "201") (name "unconnected-(U1-CBUS3-Pad14)") (class "Default")
      (node (ref "U1") (pin "14") (pinfunction "CBUS3_14") (pintype "bidirectional"))
    )
    (net (code "202") (name "unconnected-(U1-CBUS4-Pad12)") (class "Default")
      (node (ref "U1") (pin "12") (pinfunction "CBUS4_12") (pintype "bidirectional"))
    )
    (net (code "203") (name "unconnected-(U1-CTS#-Pad11)") (class "Default")
      (node (ref "U1") (pin "11") (pinfunction "CTS#_11") (pintype "input"))
    )
    (net (code "204") (name "unconnected-(U1-DCD#-Pad10)") (class "Default")
      (node (ref "U1") (pin "10") (pinfunction "DCD#_10") (pintype "input"))
    )
    (net (code "205") (name "unconnected-(U1-DSR#-Pad9)") (class "Default")
      (node (ref "U1") (pin "9") (pinfunction "DSR#_9") (pintype "input"))
    )
    (net (code "206") (name "unconnected-(U1-DTR#-Pad2)") (class "Default")
      (node (ref "U1") (pin "2") (pinfunction "DTR#_2") (pintype "output"))
    )
    (net (code "207") (name "unconnected-(U1-OSCI-Pad27)") (class "Default")
      (node (ref "U1") (pin "27") (pinfunction "OSCI_27") (pintype "input"))
    )
    (net (code "208") (name "unconnected-(U1-OSCO-Pad28)") (class "Default")
      (node (ref "U1") (pin "28") (pinfunction "OSCO_28") (pintype "output"))
    )
    (net (code "209") (name "unconnected-(U1-RI#-Pad6)") (class "Default")
      (node (ref "U1") (pin "6") (pinfunction "RI#_6") (pintype "input"))
    )
    (net (code "210") (name "unconnected-(U1-RTS#-Pad3)") (class "Default")
      (node (ref "U1") (pin "3") (pinfunction "RTS#_3") (pintype "output"))
    )
  )
)
